# uv.net
KiCad netlist of a schematic drawn in Altium Designer
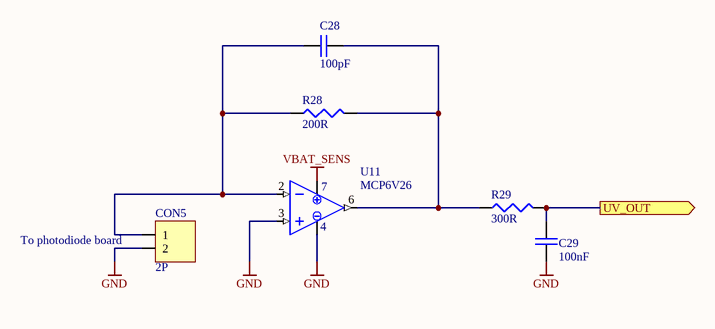
[diagram p0: uv.SchDoc]

(export (version "E")
  (design (tool "Eeschema 10.0.6"))
  (components
    (comp (ref "C28")
      (value "100pF")
      (footprint "0603")
      (description "Capacitor")
      (fields (field (name "OWNER") "Nuno Brum"))
      (libsource (lib "Alcetronics_Devices") (part "CAP"))
    )
    (comp (ref "C29")
      (value "100nF")
      (footprint "0603")
      (description "Capacitor")
      (fields (field (name "OWNER") "Nuno Brum"))
      (libsource (lib "Alcetronics_Devices") (part "CAP"))
    )
    (comp (ref "CON5")
      (value "2P")
      (footprint "INTERLOCK2-5MM-FIXED")
      (description "Connector 2 pins")
      (fields (field (name "OWNER") "Rui Rebelo"))
      (libsource (lib "Alcetronics_EM") (part "CON02"))
    )
    (comp (ref "R28")
      (value "200R")
      (footprint "0603")
      (description "Resistor")
      (fields (field (name "OWNER") "Nuno Brum"))
      (libsource (lib "Alcetronics_Devices") (part "RES"))
    )
    (comp (ref "R29")
      (value "300R")
      (footprint "0603")
      (description "Resistor")
      (fields (field (name "OWNER") "Nuno Brum"))
      (libsource (lib "Alcetronics_Devices") (part "RES"))
    )
    (comp (ref "U11")
      (value "MCP6V26")
      (footprint "SOIC-8")
      (description "Low-Offset Opamp")
      (libsource (lib "Alcetronics_IC") (part "MCP6V26"))
    )
  )
  (nets
    (net (code "1") (name "/UV_OUT") (class "Default")
      (node (ref "C29") (pin "2") (pinfunction "2_2") (pintype "passive"))
      (node (ref "R29") (pin "2") (pinfunction "2_2") (pintype "passive"))
    )
    (net (code "2") (name "GND") (class "Default")
      (node (ref "C29") (pin "1") (pinfunction "1_1") (pintype "passive"))
      (node (ref "CON5") (pin "2") (pinfunction "2_2") (pintype "passive"))
      (node (ref "U11") (pin "3") (pinfunction "INP_3") (pintype "input"))
      (node (ref "U11") (pin "4") (pinfunction "VSS_4") (pintype "power_in"))
    )
    (net (code "3") (name "Net-(U11-INN)") (class "Default")
      (node (ref "C28") (pin "1") (pinfunction "1_1") (pintype "passive"))
      (node (ref "CON5") (pin "1") (pinfunction "1_1") (pintype "passive"))
      (node (ref "R28") (pin "1") (pinfunction "1_1") (pintype "passive"))
      (node (ref "U11") (pin "2") (pinfunction "INN_2") (pintype "input"))
    )
    (net (code "4") (name "Net-(U11-VOUT)") (class "Default")
      (node (ref "C28") (pin "2") (pinfunction "2_2") (pintype "passive"))
      (node (ref "R28") (pin "2") (pinfunction "2_2") (pintype "passive"))
      (node (ref "R29") (pin "1") (pinfunction "1_1") (pintype "passive"))
      (node (ref "U11") (pin "6") (pinfunction "VOUT_6") (pintype "output"))
    )
    (net (code "5") (name "VBAT_SENS") (class "Default")
      (node (ref "U11") (pin "7") (pinfunction "VDD_7") (pintype "power_in"))
    )
  )
)
